# AGRIBOT.net
KiCad netlist of a schematic drawn in EasyEDA
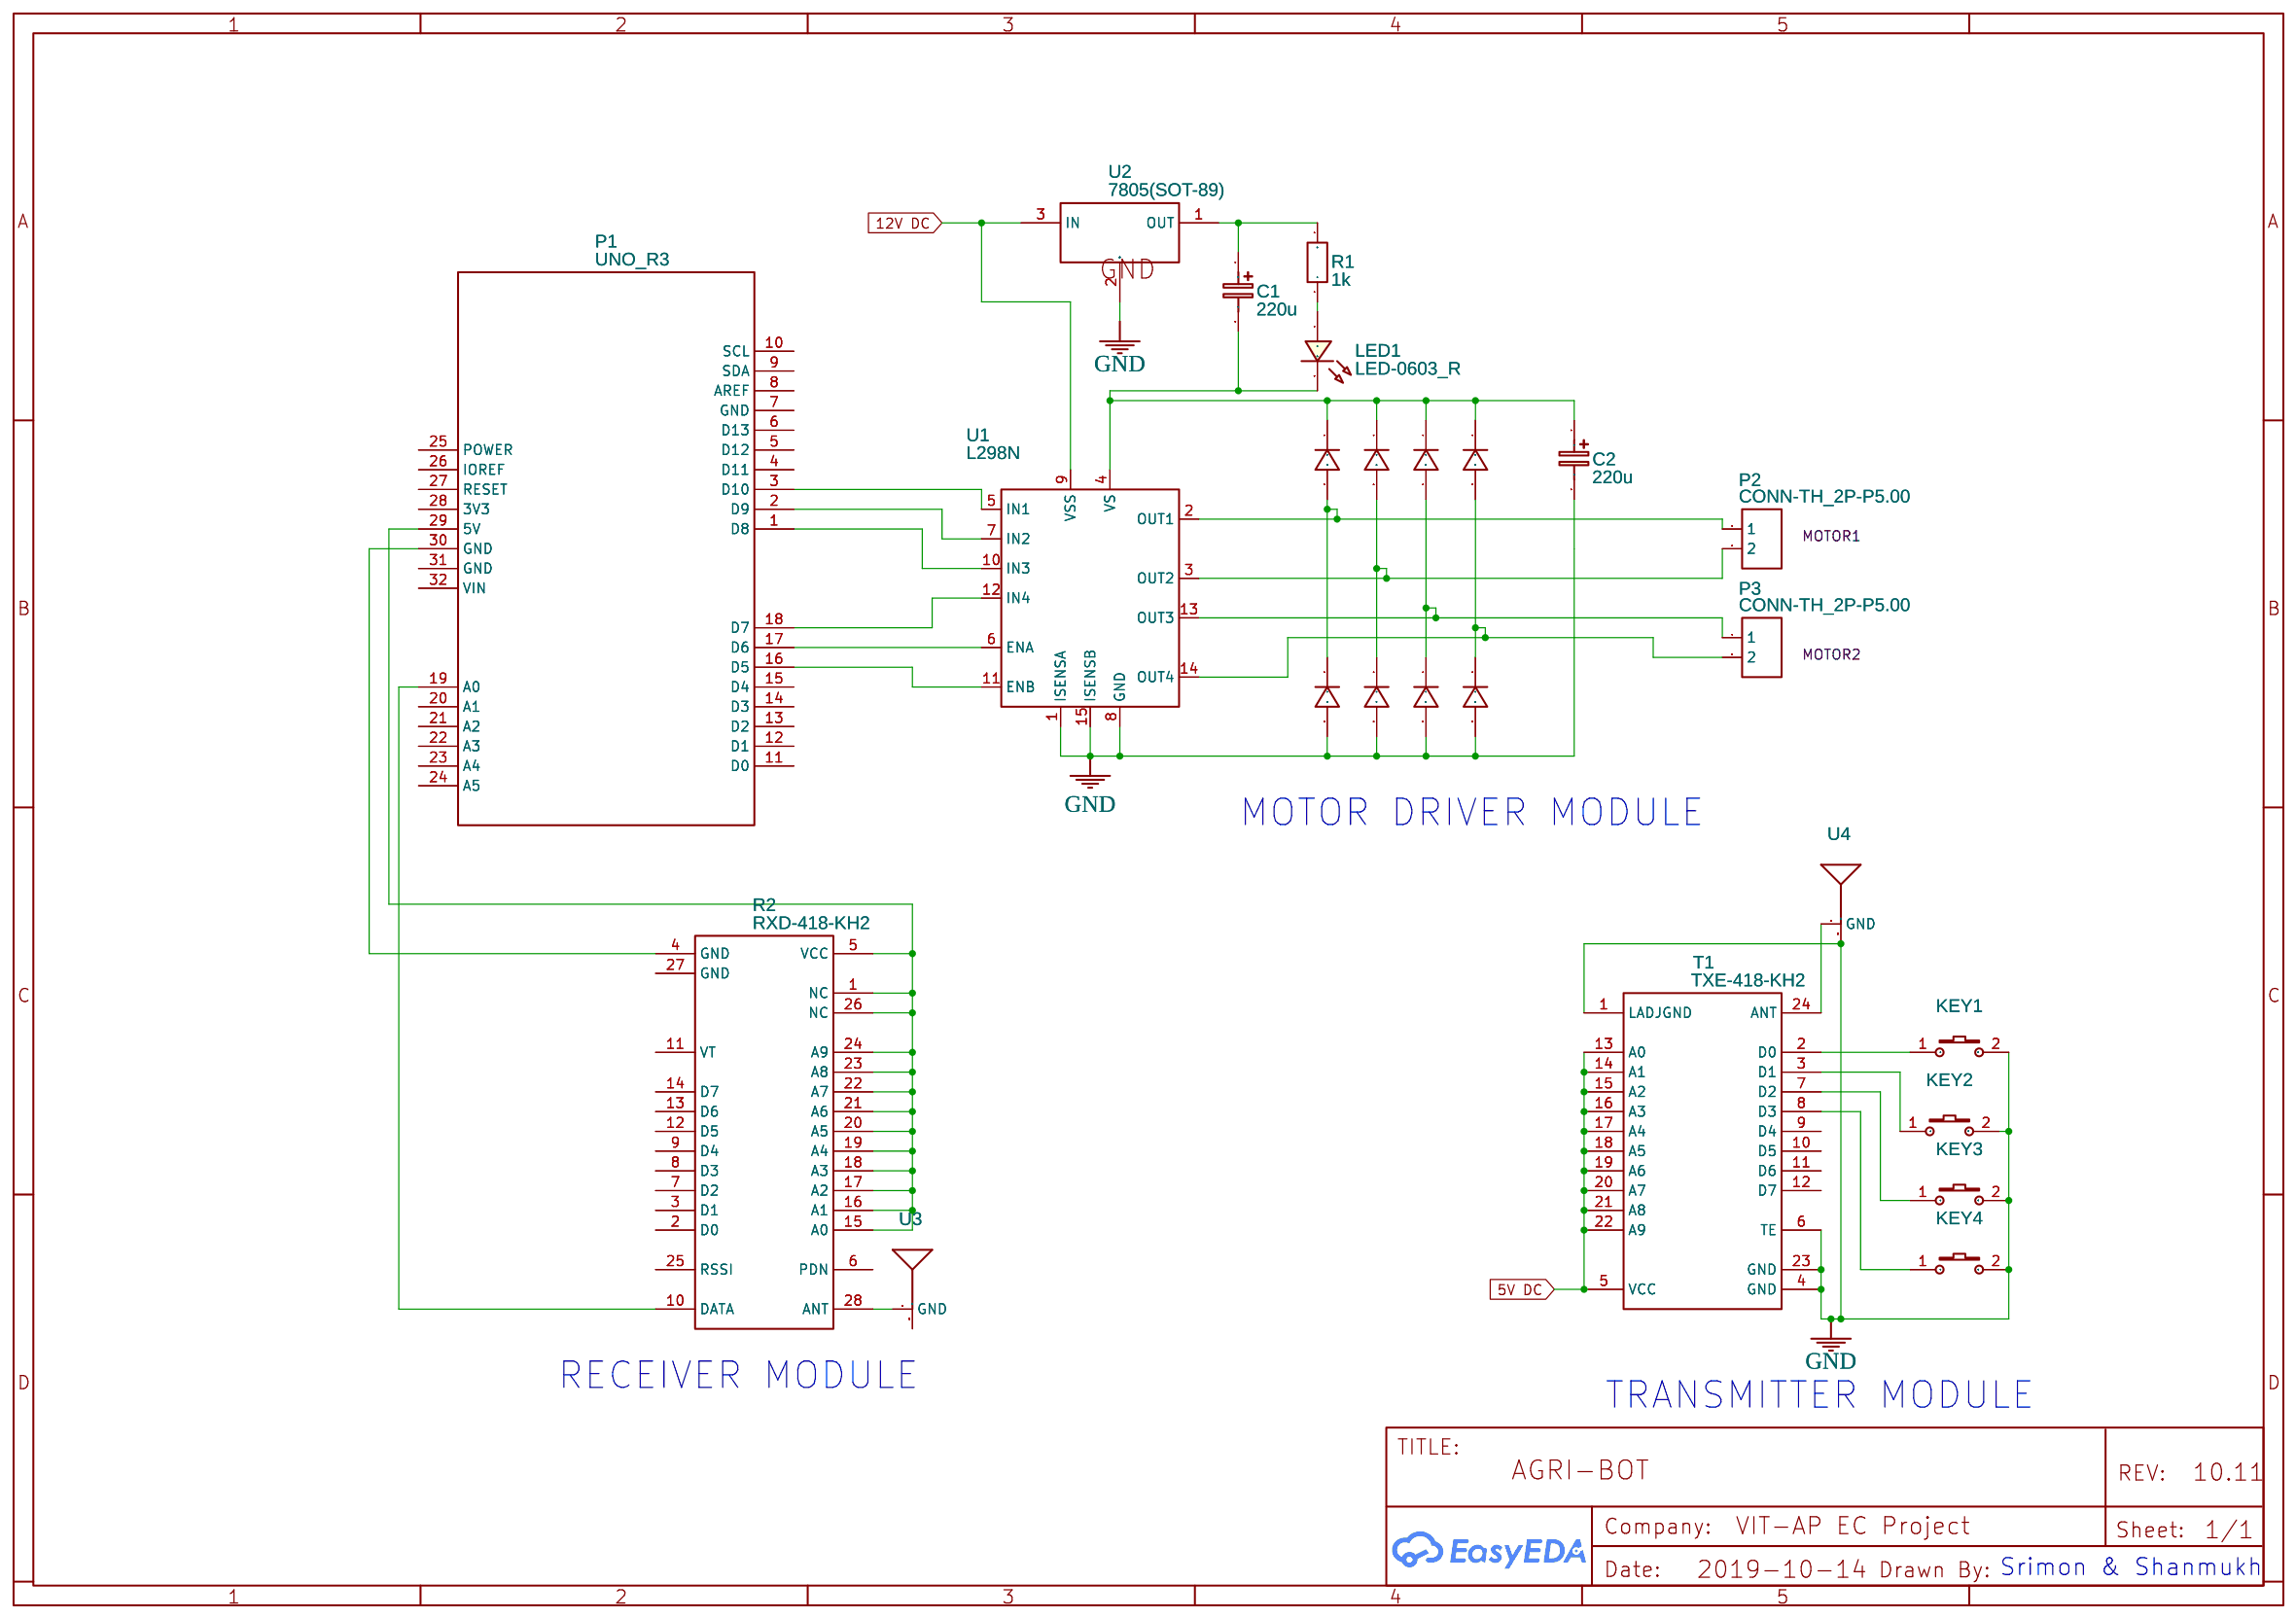
[diagram p0: schematic sheet]

(export (version "E")
  (design (tool "Eeschema 10.0.6"))
  (components
    (comp (ref "C1") (value "220u") (libsource (lib "") (part "C_Tan_SMD_A_EU")))
    (comp (ref "C2") (value "220u") (libsource (lib "") (part "C_Tan_SMD_A_EU")))
    (comp (ref "D1")
      (value "1N4007W")
      (fields (field (name "BOM_Supplier Part") "C328592"))
      (libsource (lib "") (part "1N4007W"))
    )
    (comp (ref "D2")
      (value "1N4007W")
      (fields (field (name "BOM_Supplier Part") "C328592"))
      (libsource (lib "") (part "1N4007W"))
    )
    (comp (ref "D3")
      (value "1N4007W")
      (fields (field (name "BOM_Supplier Part") "C328592"))
      (libsource (lib "") (part "1N4007W"))
    )
    (comp (ref "D4")
      (value "1N4007W")
      (fields (field (name "BOM_Supplier Part") "C328592"))
      (libsource (lib "") (part "1N4007W"))
    )
    (comp (ref "D5")
      (value "1N4007W")
      (fields (field (name "BOM_Supplier Part") "C328592"))
      (libsource (lib "") (part "1N4007W"))
    )
    (comp (ref "D6")
      (value "1N4007W")
      (fields (field (name "BOM_Supplier Part") "C328592"))
      (libsource (lib "") (part "1N4007W"))
    )
    (comp (ref "D7")
      (value "1N4007W")
      (fields (field (name "BOM_Supplier Part") "C328592"))
      (libsource (lib "") (part "1N4007W"))
    )
    (comp (ref "D8")
      (value "1N4007W")
      (fields (field (name "BOM_Supplier Part") "C328592"))
      (libsource (lib "") (part "1N4007W"))
    )
    (comp (ref "KEY1")
      (value "K2-3.6×6.1_SMD")
      (fields
        (field (name "BOM_Manufacturer Part") "K2-1107ST-A4SW-06")
        (field (name "BOM_Supplier Part") "C118141")
      )
      (libsource (lib "") (part "K2-3.6×6.1_SMD"))
    )
    (comp (ref "KEY2")
      (value "K2-3.6×6.1_SMD")
      (fields
        (field (name "BOM_Manufacturer Part") "K2-1107ST-A4SW-06")
        (field (name "BOM_Supplier Part") "C118141")
      )
      (libsource (lib "") (part "K2-3.6×6.1_SMD"))
    )
    (comp (ref "KEY3")
      (value "K2-3.6×6.1_SMD")
      (fields
        (field (name "BOM_Manufacturer Part") "K2-1107ST-A4SW-06")
        (field (name "BOM_Supplier Part") "C118141")
      )
      (libsource (lib "") (part "K2-3.6×6.1_SMD"))
    )
    (comp (ref "KEY4")
      (value "K2-3.6×6.1_SMD")
      (fields
        (field (name "BOM_Manufacturer Part") "K2-1107ST-A4SW-06")
        (field (name "BOM_Supplier Part") "C118141")
      )
      (libsource (lib "") (part "K2-3.6×6.1_SMD"))
    )
    (comp (ref "LED1")
      (value "LED-0603_R")
      (fields
        (field (name "BOM_Manufacturer Part") "19-217/R6C-AL1M2VY/3T")
        (field (name "BOM_Supplier Part") "C72044")
      )
      (libsource (lib "") (part "LED-0603_R"))
    )
    (comp (ref "P1") (value "UNO_R3") (libsource (lib "") (part "UNO_R3")))
    (comp (ref "P2") (value "CONN-TH_2P-P5.00") (libsource (lib "") (part "CONN-TH_2P-P5.00")))
    (comp (ref "P3") (value "CONN-TH_2P-P5.00") (libsource (lib "") (part "CONN-TH_2P-P5.00")))
    (comp (ref "R1") (value "1k") (libsource (lib "") (part "R_0603_EU")))
    (comp (ref "R2") (value "RXD-418-KH2") (libsource (lib "") (part "RXD-418-KH2")))
    (comp (ref "T1") (value "TXE-418-KH2") (libsource (lib "") (part "TXE-418-KH2")))
    (comp (ref "U1") (value "L298N") (libsource (lib "") (part "L298N")))
    (comp (ref "U2")
      (value "7805(SOT-89)")
      (fields (field (name "BOM_Manufacturer Part") "CJ78L05") (field (name "BOM_Supplier Part") "C2079"))
      (libsource (lib "") (part "7805(SOT-89)"))
    )
    (comp (ref "U3") (value "ANTENNA-GND24GHZ") (libsource (lib "") (part "ANTENNA-GND24GHZ")))
    (comp (ref "U4") (value "ANTENNA-GND24GHZ") (libsource (lib "") (part "ANTENNA-GND24GHZ")))
  )
  (nets
    (net (code "3") (name "5V DC") (class "Default")
      (node (ref "T1") (pin "13") (pinfunction "A0_13") (pintype "unspecified"))
      (node (ref "T1") (pin "14") (pinfunction "A1_14") (pintype "unspecified"))
      (node (ref "T1") (pin "15") (pinfunction "A2_15") (pintype "unspecified"))
      (node (ref "T1") (pin "16") (pinfunction "A3_16") (pintype "unspecified"))
      (node (ref "T1") (pin "17") (pinfunction "A4_17") (pintype "unspecified"))
      (node (ref "T1") (pin "18") (pinfunction "A5_18") (pintype "unspecified"))
      (node (ref "T1") (pin "19") (pinfunction "A6_19") (pintype "unspecified"))
      (node (ref "T1") (pin "20") (pinfunction "A7_20") (pintype "unspecified"))
      (node (ref "T1") (pin "21") (pinfunction "A8_21") (pintype "unspecified"))
      (node (ref "T1") (pin "22") (pinfunction "A9_22") (pintype "unspecified"))
      (node (ref "T1") (pin "5") (pinfunction "VCC_5") (pintype "passive"))
    )
    (net (code "4") (name "12V DC") (class "Default")
      (node (ref "U1") (pin "9") (pinfunction "VSS_9") (pintype "unspecified"))
      (node (ref "U2") (pin "3") (pinfunction "IN_3") (pintype "passive"))
    )
    (net (code "5") (name "GND") (class "Default")
      (node (ref "C2") (pin "2") (pinfunction "2_2") (pintype "unspecified"))
      (node (ref "D2") (pin "2") (pinfunction "2_2") (pintype "unspecified"))
      (node (ref "D6") (pin "2") (pinfunction "2_2") (pintype "unspecified"))
      (node (ref "D7") (pin "2") (pinfunction "2_2") (pintype "unspecified"))
      (node (ref "D8") (pin "2") (pinfunction "2_2") (pintype "unspecified"))
      (node (ref "KEY1") (pin "2") (pinfunction "2_2") (pintype "unspecified"))
      (node (ref "KEY2") (pin "2") (pinfunction "2_2") (pintype "unspecified"))
      (node (ref "KEY3") (pin "2") (pinfunction "2_2") (pintype "unspecified"))
      (node (ref "KEY4") (pin "2") (pinfunction "2_2") (pintype "unspecified"))
      (node (ref "T1") (pin "1") (pinfunction "LADJGND_1") (pintype "unspecified"))
      (node (ref "T1") (pin "23") (pinfunction "GND_23") (pintype "passive"))
      (node (ref "T1") (pin "4") (pinfunction "GND_4") (pintype "passive"))
      (node (ref "T1") (pin "6") (pinfunction "TE_6") (pintype "unspecified"))
      (node (ref "U1") (pin "1") (pinfunction "ISENSA_1") (pintype "unspecified"))
      (node (ref "U1") (pin "15") (pinfunction "ISENSB_15") (pintype "unspecified"))
      (node (ref "U1") (pin "8") (pinfunction "GND_8") (pintype "unspecified"))
      (node (ref "U2") (pin "2") (pinfunction "GND_2") (pintype "passive"))
      (node (ref "U4") (pin "FEED") (pinfunction "SIGNAL_FEED") (pintype "unspecified"))
    )
    (net (code "6") (name "Net-(LED1-Pad1)") (class "Default")
      (node (ref "LED1") (pin "1") (pinfunction "1_1") (pintype "unspecified"))
      (node (ref "R1") (pin "1") (pinfunction "1_1") (pintype "unspecified"))
    )
    (net (code "7") (name "Net-(P1-5V)") (class "Default")
      (node (ref "P1") (pin "29") (pinfunction "5V_29") (pintype "unspecified"))
      (node (ref "R2") (pin "1") (pinfunction "NC_1") (pintype "unspecified"))
      (node (ref "R2") (pin "15") (pinfunction "A0_15") (pintype "unspecified"))
      (node (ref "R2") (pin "16") (pinfunction "A1_16") (pintype "unspecified"))
      (node (ref "R2") (pin "17") (pinfunction "A2_17") (pintype "unspecified"))
      (node (ref "R2") (pin "18") (pinfunction "A3_18") (pintype "unspecified"))
      (node (ref "R2") (pin "19") (pinfunction "A4_19") (pintype "unspecified"))
      (node (ref "R2") (pin "20") (pinfunction "A5_20") (pintype "unspecified"))
      (node (ref "R2") (pin "21") (pinfunction "A6_21") (pintype "unspecified"))
      (node (ref "R2") (pin "22") (pinfunction "A7_22") (pintype "unspecified"))
      (node (ref "R2") (pin "23") (pinfunction "A8_23") (pintype "unspecified"))
      (node (ref "R2") (pin "24") (pinfunction "A9_24") (pintype "unspecified"))
      (node (ref "R2") (pin "26") (pinfunction "NC_26") (pintype "unspecified"))
      (node (ref "R2") (pin "5") (pinfunction "VCC_5") (pintype "passive"))
    )
    (net (code "8") (name "Net-(P1-A0)") (class "Default")
      (node (ref "P1") (pin "19") (pinfunction "A0_19") (pintype "unspecified"))
      (node (ref "R2") (pin "10") (pinfunction "DATA_10") (pintype "output"))
    )
    (net (code "9") (name "Net-(P1-D5)") (class "Default")
      (node (ref "P1") (pin "16") (pinfunction "D5_16") (pintype "unspecified"))
      (node (ref "U1") (pin "11") (pinfunction "ENB_11") (pintype "unspecified"))
    )
    (net (code "10") (name "Net-(P1-D6)") (class "Default")
      (node (ref "P1") (pin "17") (pinfunction "D6_17") (pintype "unspecified"))
      (node (ref "U1") (pin "6") (pinfunction "ENA_6") (pintype "unspecified"))
    )
    (net (code "11") (name "Net-(P1-D7)") (class "Default")
      (node (ref "P1") (pin "18") (pinfunction "D7_18") (pintype "unspecified"))
      (node (ref "U1") (pin "12") (pinfunction "IN4_12") (pintype "unspecified"))
    )
    (net (code "12") (name "Net-(P1-D8)") (class "Default")
      (node (ref "P1") (pin "1") (pinfunction "D8_1") (pintype "unspecified"))
      (node (ref "U1") (pin "10") (pinfunction "IN3_10") (pintype "unspecified"))
    )
    (net (code "13") (name "Net-(P1-D9)") (class "Default")
      (node (ref "P1") (pin "2") (pinfunction "D9_2") (pintype "unspecified"))
      (node (ref "U1") (pin "7") (pinfunction "IN2_7") (pintype "unspecified"))
    )
    (net (code "14") (name "Net-(P1-D10)") (class "Default")
      (node (ref "P1") (pin "3") (pinfunction "D10_3") (pintype "unspecified"))
      (node (ref "U1") (pin "5") (pinfunction "IN1_5") (pintype "unspecified"))
    )
    (net (code "15") (name "Net-(P1-GND-Pad30)") (class "Default")
      (node (ref "P1") (pin "30") (pinfunction "GND_30") (pintype "unspecified"))
      (node (ref "R2") (pin "4") (pinfunction "GND_4") (pintype "passive"))
    )
    (net (code "16") (name "Net-(R2-ANT)") (class "Default")
      (node (ref "R2") (pin "28") (pinfunction "ANT_28") (pintype "unspecified"))
      (node (ref "U3") (pin "GND") (pinfunction "GND_GND") (pintype "unspecified"))
    )
    (net (code "17") (name "Net-(T1-ANT)") (class "Default")
      (node (ref "T1") (pin "24") (pinfunction "ANT_24") (pintype "output"))
      (node (ref "U4") (pin "GND") (pinfunction "GND_GND") (pintype "unspecified"))
    )
    (net (code "18") (name "Net-(T1-D0)") (class "Default")
      (node (ref "KEY1") (pin "1") (pinfunction "1_1") (pintype "unspecified"))
      (node (ref "T1") (pin "2") (pinfunction "D0_2") (pintype "unspecified"))
    )
    (net (code "19") (name "Net-(T1-D1)") (class "Default")
      (node (ref "KEY2") (pin "1") (pinfunction "1_1") (pintype "unspecified"))
      (node (ref "T1") (pin "3") (pinfunction "D1_3") (pintype "unspecified"))
    )
    (net (code "20") (name "Net-(T1-D2)") (class "Default")
      (node (ref "KEY3") (pin "1") (pinfunction "1_1") (pintype "unspecified"))
      (node (ref "T1") (pin "7") (pinfunction "D2_7") (pintype "unspecified"))
    )
    (net (code "21") (name "Net-(T1-D3)") (class "Default")
      (node (ref "KEY4") (pin "1") (pinfunction "1_1") (pintype "unspecified"))
      (node (ref "T1") (pin "8") (pinfunction "D3_8") (pintype "unspecified"))
    )
    (net (code "22") (name "Net-(U1-OUT1)") (class "Default")
      (node (ref "D1") (pin "2") (pinfunction "2_2") (pintype "unspecified"))
      (node (ref "D2") (pin "1") (pinfunction "1_1") (pintype "unspecified"))
      (node (ref "P2") (pin "1") (pinfunction "1_1") (pintype "unspecified"))
      (node (ref "U1") (pin "2") (pinfunction "OUT1_2") (pintype "unspecified"))
    )
    (net (code "23") (name "Net-(U1-OUT2)") (class "Default")
      (node (ref "D3") (pin "2") (pinfunction "2_2") (pintype "unspecified"))
      (node (ref "D6") (pin "1") (pinfunction "1_1") (pintype "unspecified"))
      (node (ref "P2") (pin "2") (pinfunction "2_2") (pintype "unspecified"))
      (node (ref "U1") (pin "3") (pinfunction "OUT2_3") (pintype "unspecified"))
    )
    (net (code "24") (name "Net-(U1-OUT3)") (class "Default")
      (node (ref "D4") (pin "2") (pinfunction "2_2") (pintype "unspecified"))
      (node (ref "D7") (pin "1") (pinfunction "1_1") (pintype "unspecified"))
      (node (ref "P3") (pin "1") (pinfunction "1_1") (pintype "unspecified"))
      (node (ref "U1") (pin "13") (pinfunction "OUT3_13") (pintype "unspecified"))
    )
    (net (code "25") (name "Net-(U1-OUT4)") (class "Default")
      (node (ref "D5") (pin "2") (pinfunction "2_2") (pintype "unspecified"))
      (node (ref "D8") (pin "1") (pinfunction "1_1") (pintype "unspecified"))
      (node (ref "P3") (pin "2") (pinfunction "2_2") (pintype "unspecified"))
      (node (ref "U1") (pin "14") (pinfunction "OUT4_14") (pintype "unspecified"))
    )
    (net (code "26") (name "Net-(U1-VS)") (class "Default")
      (node (ref "C1") (pin "2") (pinfunction "2_2") (pintype "unspecified"))
      (node (ref "C2") (pin "1") (pinfunction "1_1") (pintype "unspecified"))
      (node (ref "D1") (pin "1") (pinfunction "1_1") (pintype "unspecified"))
      (node (ref "D3") (pin "1") (pinfunction "1_1") (pintype "unspecified"))
      (node (ref "D4") (pin "1") (pinfunction "1_1") (pintype "unspecified"))
      (node (ref "D5") (pin "1") (pinfunction "1_1") (pintype "unspecified"))
      (node (ref "LED1") (pin "2") (pinfunction "2_2") (pintype "unspecified"))
      (node (ref "U1") (pin "4") (pinfunction "VS_4") (pintype "unspecified"))
    )
    (net (code "27") (name "Net-(U2-OUT)") (class "Default")
      (node (ref "C1") (pin "1") (pinfunction "1_1") (pintype "unspecified"))
      (node (ref "R1") (pin "2") (pinfunction "2_2") (pintype "unspecified"))
      (node (ref "U2") (pin "1") (pinfunction "OUT_1") (pintype "passive"))
    )
    (net (code "28") (name "unconnected-(P1-3V3-Pad28)") (class "Default")
      (node (ref "P1") (pin "28") (pinfunction "3V3_28") (pintype "unspecified"))
    )
    (net (code "29") (name "unconnected-(P1-A1-Pad20)") (class "Default")
      (node (ref "P1") (pin "20") (pinfunction "A1_20") (pintype "unspecified"))
    )
    (net (code "30") (name "unconnected-(P1-A2-Pad21)") (class "Default")
      (node (ref "P1") (pin "21") (pinfunction "A2_21") (pintype "unspecified"))
    )
    (net (code "31") (name "unconnected-(P1-A3-Pad22)") (class "Default")
      (node (ref "P1") (pin "22") (pinfunction "A3_22") (pintype "unspecified"))
    )
    (net (code "32") (name "unconnected-(P1-A4-Pad23)") (class "Default")
      (node (ref "P1") (pin "23") (pinfunction "A4_23") (pintype "unspecified"))
    )
    (net (code "33") (name "unconnected-(P1-A5-Pad24)") (class "Default")
      (node (ref "P1") (pin "24") (pinfunction "A5_24") (pintype "unspecified"))
    )
    (net (code "34") (name "unconnected-(P1-AREF-Pad8)") (class "Default")
      (node (ref "P1") (pin "8") (pinfunction "AREF_8") (pintype "unspecified"))
    )
    (net (code "35") (name "unconnected-(P1-D0-Pad11)") (class "Default")
      (node (ref "P1") (pin "11") (pinfunction "D0_11") (pintype "unspecified"))
    )
    (net (code "36") (name "unconnected-(P1-D1-Pad12)") (class "Default")
      (node (ref "P1") (pin "12") (pinfunction "D1_12") (pintype "unspecified"))
    )
    (net (code "37") (name "unconnected-(P1-D2-Pad13)") (class "Default")
      (node (ref "P1") (pin "13") (pinfunction "D2_13") (pintype "unspecified"))
    )
    (net (code "38") (name "unconnected-(P1-D3-Pad14)") (class "Default")
      (node (ref "P1") (pin "14") (pinfunction "D3_14") (pintype "unspecified"))
    )
    (net (code "39") (name "unconnected-(P1-D4-Pad15)") (class "Default")
      (node (ref "P1") (pin "15") (pinfunction "D4_15") (pintype "unspecified"))
    )
    (net (code "40") (name "unconnected-(P1-D11-Pad4)") (class "Default")
      (node (ref "P1") (pin "4") (pinfunction "D11_4") (pintype "unspecified"))
    )
    (net (code "41") (name "unconnected-(P1-D12-Pad5)") (class "Default")
      (node (ref "P1") (pin "5") (pinfunction "D12_5") (pintype "unspecified"))
    )
    (net (code "42") (name "unconnected-(P1-D13-Pad6)") (class "Default")
      (node (ref "P1") (pin "6") (pinfunction "D13_6") (pintype "unspecified"))
    )
    (net (code "43") (name "unconnected-(P1-GND-Pad7)") (class "Default")
      (node (ref "P1") (pin "7") (pinfunction "GND_7") (pintype "unspecified"))
    )
    (net (code "44") (name "unconnected-(P1-GND-Pad31)") (class "Default")
      (node (ref "P1") (pin "31") (pinfunction "GND_31") (pintype "unspecified"))
    )
    (net (code "45") (name "unconnected-(P1-IOREF-Pad26)") (class "Default")
      (node (ref "P1") (pin "26") (pinfunction "IOREF_26") (pintype "unspecified"))
    )
    (net (code "46") (name "unconnected-(P1-POWER-Pad25)") (class "Default")
      (node (ref "P1") (pin "25") (pinfunction "POWER_25") (pintype "unspecified"))
    )
    (net (code "47") (name "unconnected-(P1-RESET-Pad27)") (class "Default")
      (node (ref "P1") (pin "27") (pinfunction "RESET_27") (pintype "unspecified"))
    )
    (net (code "48") (name "unconnected-(P1-SCL-Pad10)") (class "Default")
      (node (ref "P1") (pin "10") (pinfunction "SCL_10") (pintype "unspecified"))
    )
    (net (code "49") (name "unconnected-(P1-SDA-Pad9)") (class "Default")
      (node (ref "P1") (pin "9") (pinfunction "SDA_9") (pintype "unspecified"))
    )
    (net (code "50") (name "unconnected-(P1-VIN-Pad32)") (class "Default")
      (node (ref "P1") (pin "32") (pinfunction "VIN_32") (pintype "unspecified"))
    )
    (net (code "51") (name "unconnected-(R2-D0-Pad2)") (class "Default")
      (node (ref "R2") (pin "2") (pinfunction "D0_2") (pintype "output"))
    )
    (net (code "52") (name "unconnected-(R2-D1-Pad3)") (class "Default")
      (node (ref "R2") (pin "3") (pinfunction "D1_3") (pintype "output"))
    )
    (net (code "53") (name "unconnected-(R2-D2-Pad7)") (class "Default")
      (node (ref "R2") (pin "7") (pinfunction "D2_7") (pintype "output"))
    )
    (net (code "54") (name "unconnected-(R2-D3-Pad8)") (class "Default")
      (node (ref "R2") (pin "8") (pinfunction "D3_8") (pintype "output"))
    )
    (net (code "55") (name "unconnected-(R2-D4-Pad9)") (class "Default")
      (node (ref "R2") (pin "9") (pinfunction "D4_9") (pintype "output"))
    )
    (net (code "56") (name "unconnected-(R2-D5-Pad12)") (class "Default")
      (node (ref "R2") (pin "12") (pinfunction "D5_12") (pintype "output"))
    )
    (net (code "57") (name "unconnected-(R2-D6-Pad13)") (class "Default")
      (node (ref "R2") (pin "13") (pinfunction "D6_13") (pintype "output"))
    )
    (net (code "58") (name "unconnected-(R2-D7-Pad14)") (class "Default")
      (node (ref "R2") (pin "14") (pinfunction "D7_14") (pintype "output"))
    )
    (net (code "59") (name "unconnected-(R2-GND-Pad27)") (class "Default")
      (node (ref "R2") (pin "27") (pinfunction "GND_27") (pintype "passive"))
    )
    (net (code "60") (name "unconnected-(R2-PDN-Pad6)") (class "Default")
      (node (ref "R2") (pin "6") (pinfunction "PDN_6") (pintype "unspecified"))
    )
    (net (code "61") (name "unconnected-(R2-RSSI-Pad25)") (class "Default")
      (node (ref "R2") (pin "25") (pinfunction "RSSI_25") (pintype "output"))
    )
    (net (code "62") (name "unconnected-(R2-VT-Pad11)") (class "Default")
      (node (ref "R2") (pin "11") (pinfunction "VT_11") (pintype "output"))
    )
    (net (code "63") (name "unconnected-(T1-D4-Pad9)") (class "Default")
      (node (ref "T1") (pin "9") (pinfunction "D4_9") (pintype "unspecified"))
    )
    (net (code "64") (name "unconnected-(T1-D5-Pad10)") (class "Default")
      (node (ref "T1") (pin "10") (pinfunction "D5_10") (pintype "unspecified"))
    )
    (net (code "65") (name "unconnected-(T1-D6-Pad11)") (class "Default")
      (node (ref "T1") (pin "11") (pinfunction "D6_11") (pintype "unspecified"))
    )
    (net (code "66") (name "unconnected-(T1-D7-Pad12)") (class "Default")
      (node (ref "T1") (pin "12") (pinfunction "D7_12") (pintype "unspecified"))
    )
    (net (code "67") (name "unconnected-(U3-SIGNAL-PadFEED)") (class "Default")
      (node (ref "U3") (pin "FEED") (pinfunction "SIGNAL_FEED") (pintype "unspecified"))
    )
  )
)
